# Reference_Adapter.net
KiCad netlist of a schematic drawn in EAGLE
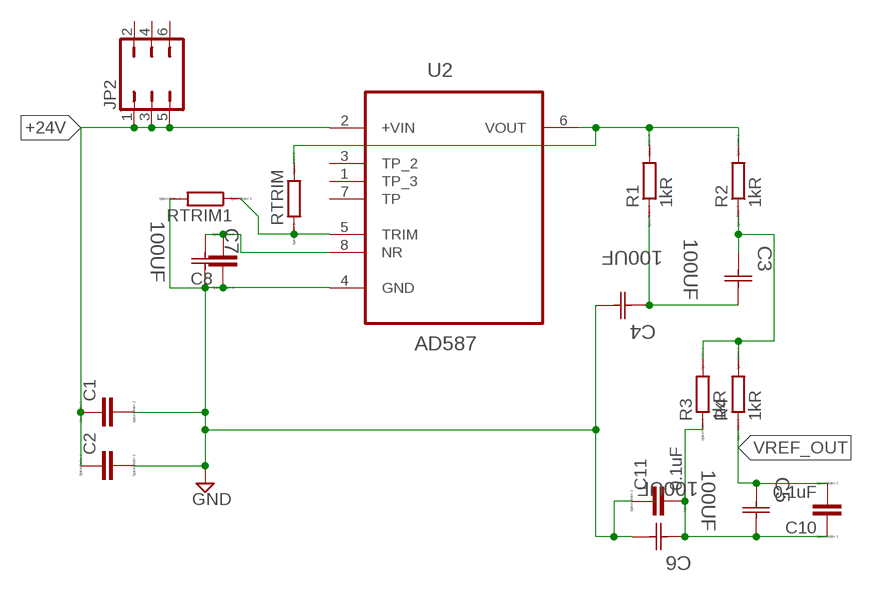
[diagram p0: schematic, sheet 1]

(export (version "E")
  (design (tool "Eeschema 10.0.6"))
  (components
    (comp (ref "C1") (value "C") (footprint "eagle-import:C0805") (libsource (lib "eagle-import") (part "C")))
    (comp (ref "C2")
      (value "CC0603")
      (footprint "eagle-import:C0603")
      (libsource (lib "eagle-import") (part "CC0603"))
    )
    (comp (ref "C3")
      (value "100UF")
      (footprint "eagle-import:CAPCP7343X430N")
      (fields (field (name "MPN") "TPSE107M020R0150"))
      (libsource (lib "eagle-import") (part "TPSE107M020R0150"))
    )
    (comp (ref "C4")
      (value "100UF")
      (footprint "eagle-import:CAPCP7343X430N")
      (fields (field (name "MPN") "TPSE107M020R0150"))
      (libsource (lib "eagle-import") (part "TPSE107M020R0150"))
    )
    (comp (ref "C5")
      (value "100UF")
      (footprint "eagle-import:CAPCP7343X430N")
      (fields (field (name "MPN") "TPSE107M020R0150"))
      (libsource (lib "eagle-import") (part "TPSE107M020R0150"))
    )
    (comp (ref "C6")
      (value "100UF")
      (footprint "eagle-import:CAPCP7343X430N")
      (fields (field (name "MPN") "TPSE107M020R0150"))
      (libsource (lib "eagle-import") (part "TPSE107M020R0150"))
    )
    (comp (ref "C7")
      (value "100UF")
      (footprint "eagle-import:CAPCP7343X430N")
      (fields (field (name "MPN") "TPSE107M020R0150"))
      (libsource (lib "eagle-import") (part "TPSE107M020R0150"))
    )
    (comp (ref "C8") (value "C") (footprint "eagle-import:C0805") (libsource (lib "eagle-import") (part "C")))
    (comp (ref "C10")
      (value "0.1uF")
      (footprint "eagle-import:C0603")
      (libsource (lib "eagle-import") (part "CC0603"))
    )
    (comp (ref "C11")
      (value "0.1uF")
      (footprint "eagle-import:C0603")
      (libsource (lib "eagle-import") (part "CC0603"))
    )
    (comp (ref "JP2")
      (value "JP3Q")
      (footprint "eagle-import:JP3Q")
      (libsource (lib "eagle-import") (part "JP3Q"))
    )
    (comp (ref "R1")
      (value "1kR")
      (footprint "eagle-import:R0805")
      (libsource (lib "eagle-import") (part "R"))
    )
    (comp (ref "R2")
      (value "1kR")
      (footprint "eagle-import:R0805")
      (libsource (lib "eagle-import") (part "R"))
    )
    (comp (ref "R3")
      (value "1kR")
      (footprint "eagle-import:R0805")
      (libsource (lib "eagle-import") (part "R"))
    )
    (comp (ref "R4")
      (value "1kR")
      (footprint "eagle-import:R0805")
      (libsource (lib "eagle-import") (part "R"))
    )
    (comp (ref "RTRIM")
      (value "R")
      (footprint "eagle-import:R0805")
      (libsource (lib "eagle-import") (part "R"))
    )
    (comp (ref "RTRIM1")
      (value "R")
      (footprint "eagle-import:R0805")
      (libsource (lib "eagle-import") (part "R"))
    )
    (comp (ref "U2")
      (value "AD587")
      (footprint "eagle-import:SOIC127P600X175-8N")
      (fields (field (name "MPN") "AD587JRZ"))
      (libsource (lib "eagle-import") (part "AD587JRZ"))
    )
  )
  (nets
    (net (code "1") (name "+24V") (class "Default")
      (node (ref "C1") (pin "1") (pinfunction "1_1") (pintype "passive"))
      (node (ref "C2") (pin "1") (pinfunction "1_1") (pintype "passive"))
      (node (ref "JP2") (pin "1") (pinfunction "1_1") (pintype "passive"))
      (node (ref "JP2") (pin "3") (pinfunction "3_3") (pintype "passive"))
      (node (ref "JP2") (pin "5") (pinfunction "5_5") (pintype "passive"))
      (node (ref "U2") (pin "2") (pinfunction "+VIN_2") (pintype "power_in"))
    )
    (net (code "2") (name "GND") (class "Default")
      (node (ref "C1") (pin "2") (pinfunction "2_2") (pintype "passive"))
      (node (ref "C11") (pin "1") (pinfunction "1_1") (pintype "passive"))
      (node (ref "C2") (pin "2") (pinfunction "2_2") (pintype "passive"))
      (node (ref "C4") (pin "2") (pinfunction "2_2") (pintype "passive"))
      (node (ref "C6") (pin "2") (pinfunction "2_2") (pintype "passive"))
      (node (ref "C7") (pin "2") (pinfunction "2_2") (pintype "passive"))
      (node (ref "C8") (pin "1") (pinfunction "1_1") (pintype "passive"))
      (node (ref "RTRIM1") (pin "2") (pinfunction "2_2") (pintype "passive"))
      (node (ref "U2") (pin "4") (pinfunction "GND_4") (pintype "passive"))
    )
    (net (code "3") (name "Net-(C3-Pad1)") (class "Default")
      (node (ref "C3") (pin "1") (pinfunction "1_1") (pintype "passive"))
      (node (ref "R2") (pin "1") (pinfunction "1_1") (pintype "passive"))
      (node (ref "R3") (pin "2") (pinfunction "2_2") (pintype "passive"))
      (node (ref "R4") (pin "2") (pinfunction "2_2") (pintype "passive"))
    )
    (net (code "4") (name "Net-(C3-Pad2)") (class "Default")
      (node (ref "C3") (pin "2") (pinfunction "2_2") (pintype "passive"))
      (node (ref "C4") (pin "1") (pinfunction "1_1") (pintype "passive"))
      (node (ref "R1") (pin "1") (pinfunction "1_1") (pintype "passive"))
    )
    (net (code "5") (name "Net-(C10-Pad1)") (class "Default")
      (node (ref "C10") (pin "1") (pinfunction "1_1") (pintype "passive"))
      (node (ref "C11") (pin "2") (pinfunction "2_2") (pintype "passive"))
      (node (ref "C5") (pin "2") (pinfunction "2_2") (pintype "passive"))
      (node (ref "C6") (pin "1") (pinfunction "1_1") (pintype "passive"))
      (node (ref "R3") (pin "1") (pinfunction "1_1") (pintype "passive"))
    )
    (net (code "6") (name "Net-(U2-NR)") (class "Default")
      (node (ref "C7") (pin "1") (pinfunction "1_1") (pintype "passive"))
      (node (ref "C8") (pin "2") (pinfunction "2_2") (pintype "passive"))
      (node (ref "U2") (pin "8") (pinfunction "NR_8") (pintype "passive"))
    )
    (net (code "7") (name "Net-(U2-TRIM)") (class "Default")
      (node (ref "RTRIM") (pin "1") (pinfunction "1_1") (pintype "passive"))
      (node (ref "RTRIM1") (pin "1") (pinfunction "1_1") (pintype "passive"))
      (node (ref "U2") (pin "5") (pinfunction "TRIM_5") (pintype "passive"))
    )
    (net (code "8") (name "Net-(U2-VOUT)") (class "Default")
      (node (ref "R1") (pin "2") (pinfunction "2_2") (pintype "passive"))
      (node (ref "R2") (pin "2") (pinfunction "2_2") (pintype "passive"))
      (node (ref "RTRIM") (pin "2") (pinfunction "2_2") (pintype "passive"))
      (node (ref "U2") (pin "6") (pinfunction "VOUT_6") (pintype "output"))
    )
    (net (code "9") (name "VREF_OUT") (class "Default")
      (node (ref "C10") (pin "2") (pinfunction "2_2") (pintype "passive"))
      (node (ref "C5") (pin "1") (pinfunction "1_1") (pintype "passive"))
      (node (ref "R4") (pin "1") (pinfunction "1_1") (pintype "passive"))
    )
    (net (code "10") (name "unconnected-(JP2-Pad2)") (class "Default")
      (node (ref "JP2") (pin "2") (pinfunction "2_2") (pintype "passive"))
    )
    (net (code "11") (name "unconnected-(JP2-Pad4)") (class "Default")
      (node (ref "JP2") (pin "4") (pinfunction "4_4") (pintype "passive"))
    )
    (net (code "12") (name "unconnected-(JP2-Pad6)") (class "Default")
      (node (ref "JP2") (pin "6") (pinfunction "6_6") (pintype "passive"))
    )
    (net (code "13") (name "unconnected-(U2-TP-Pad7)") (class "Default")
      (node (ref "U2") (pin "7") (pinfunction "TP_7") (pintype "passive"))
    )
    (net (code "14") (name "unconnected-(U2-TP_2-Pad3)") (class "Default")
      (node (ref "U2") (pin "3") (pinfunction "TP_2_3") (pintype "passive"))
    )
    (net (code "15") (name "unconnected-(U2-TP_3-Pad1)") (class "Default")
      (node (ref "U2") (pin "1") (pinfunction "TP_3_1") (pintype "passive"))
    )
  )
)
